# Temp_Sensor.net
KiCad netlist of a schematic drawn in Altium Designer
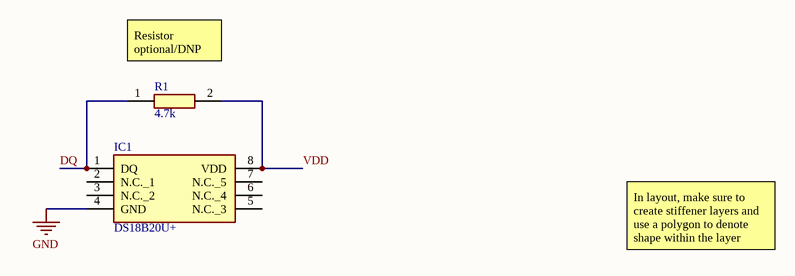
[diagram p0: Temp_Sensor.SchDoc]

(export (version "E")
  (design (tool "Eeschema 10.0.6"))
  (components
    (comp (ref "IC1")
      (value "DS18B20U+")
      (footprint "SamacSys:SOP65P490X110-8N")
      (description "Integrated Circuit")
      (fields (field (name "MOUSER PART NUMBER") "700-DS18B20U"))
      (libsource (lib "*") (part "DS18B20U+"))
    )
    (comp (ref "R1")
      (value "4.7k")
      (footprint "SamacSys:RESC1608X50N")
      (description "Resistor")
      (fields
        (field (name "MANUFACTURER_PART_NUMBER") "CRCW06034K70FKEAHP")
        (field (name "MOUSER PART NUMBER") "71-CRCW06034K70FKEAH")
      )
      (libsource (lib "*") (part "CRCW06034K70FKEAHP"))
    )
  )
  (nets
    (net (code "1") (name "/DQ") (class "Default")
      (node (ref "IC1") (pin "1") (pinfunction "DQ_1") (pintype "passive"))
      (node (ref "R1") (pin "1") (pinfunction "1_1") (pintype "passive"))
    )
    (net (code "2") (name "/VDD") (class "Default")
      (node (ref "IC1") (pin "8") (pinfunction "VDD_8") (pintype "passive"))
      (node (ref "R1") (pin "2") (pinfunction "2_2") (pintype "passive"))
    )
    (net (code "3") (name "GND") (class "Default")
      (node (ref "IC1") (pin "4") (pinfunction "GND_4") (pintype "passive"))
    )
    (net (code "4") (name "unconnected-(IC1-N.C._1-Pad2)") (class "Default")
      (node (ref "IC1") (pin "2") (pinfunction "N.C._1_2") (pintype "passive"))
    )
    (net (code "5") (name "unconnected-(IC1-N.C._2-Pad3)") (class "Default")
      (node (ref "IC1") (pin "3") (pinfunction "N.C._2_3") (pintype "passive"))
    )
    (net (code "6") (name "unconnected-(IC1-N.C._3-Pad5)") (class "Default")
      (node (ref "IC1") (pin "5") (pinfunction "N.C._3_5") (pintype "passive"))
    )
    (net (code "7") (name "unconnected-(IC1-N.C._4-Pad6)") (class "Default")
      (node (ref "IC1") (pin "6") (pinfunction "N.C._4_6") (pintype "passive"))
    )
    (net (code "8") (name "unconnected-(IC1-N.C._5-Pad7)") (class "Default")
      (node (ref "IC1") (pin "7") (pinfunction "N.C._5_7") (pintype "passive"))
    )
  )
)
